# schematic.net
KiCad netlist of a schematic drawn in EAGLE
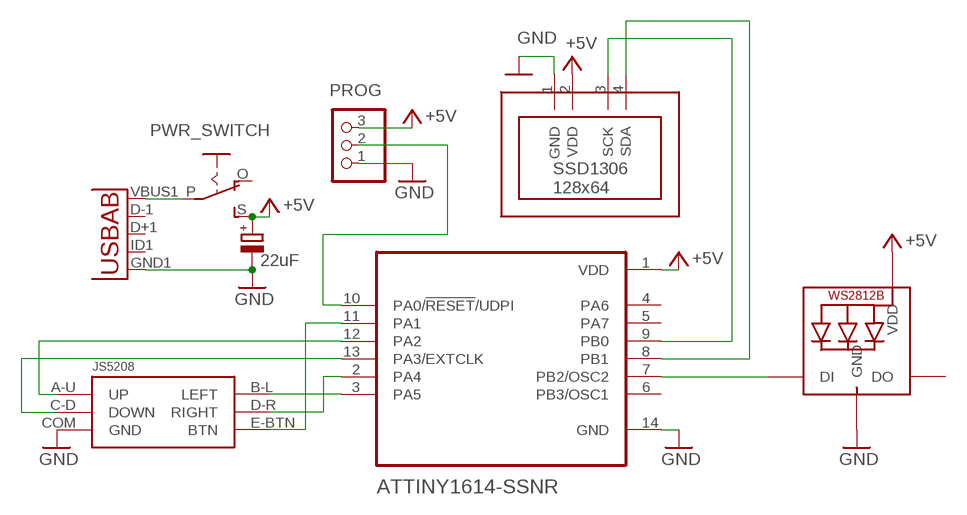
[diagram p0: schematic, sheet 1]

(export (version "E")
  (design (tool "Eeschema 10.0.6"))
  (components
    (comp (ref "C2")
      (value "22uF")
      (footprint "eagle-import:E2-4")
      (libsource (lib "eagle-import") (part "CPOL-EUE2-4"))
    )
    (comp (ref "LED1")
      (value "WS2812B5050")
      (footprint "eagle-import:WS2812B")
      (libsource (lib "eagle-import") (part "WS2812B5050"))
    )
    (comp (ref "PROG")
      (value "PINHD-1X3")
      (footprint "eagle-import:1X03")
      (libsource (lib "eagle-import") (part "PINHD-1X3"))
    )
    (comp (ref "PWR_SWITCH")
      (value "EG1218S")
      (footprint "eagle-import:EG1218")
      (fields (field (name "MF") "E-Switch") (field (name "MP") "EG1218"))
      (libsource (lib "eagle-import") (part "EG1218S"))
    )
    (comp (ref "U$1")
      (value "JS5208")
      (footprint "eagle-import:JS5208_PKG")
      (fields (field (name "MF") "E-Switch"))
      (libsource (lib "eagle-import") (part "JS5208"))
    )
    (comp (ref "U$2")
      (value "SSD1306_128X64_OLEDPINHEAD")
      (footprint "eagle-import:1X04-CLEANBIG")
      (libsource (lib "eagle-import") (part "SSD1306_128X64_OLEDPINHEAD"))
    )
    (comp (ref "U1")
      (value "ATTINY1614-SSNR")
      (footprint "eagle-import:SOIC127P600X175-14N")
      (fields (field (name "MF") "Microchip"))
      (libsource (lib "eagle-import") (part "ATTINY1614-SSNR"))
    )
    (comp (ref "U2")
      (value "USB-THROUGH")
      (footprint "eagle-import:USB-MICRO-THROUGH")
      (libsource (lib "eagle-import") (part "USB-THROUGH"))
    )
  )
  (nets
    (net (code "1") (name "+5V") (class "Default")
      (node (ref "C2") (pin "+") (pinfunction "+_+") (pintype "passive"))
      (node (ref "LED1") (pin "1-VDD") (pinfunction "VDD_1-VDD") (pintype "power_in"))
      (node (ref "PROG") (pin "3") (pinfunction "3_3") (pintype "passive"))
      (node (ref "PWR_SWITCH") (pin "S") (pinfunction "S_S") (pintype "passive"))
      (node (ref "U$2") (pin "2") (pinfunction "VDD_2") (pintype "bidirectional"))
      (node (ref "U1") (pin "1") (pinfunction "VDD_1") (pintype "power_in"))
    )
    (net (code "2") (name "GND") (class "Default")
      (node (ref "C2") (pin "-") (pinfunction "-_-") (pintype "passive"))
      (node (ref "LED1") (pin "3-GND") (pinfunction "GND_3-GND") (pintype "power_in"))
      (node (ref "PROG") (pin "1") (pinfunction "1_1") (pintype "passive"))
      (node (ref "U$1") (pin "COM") (pinfunction "GND_COM") (pintype "bidirectional"))
      (node (ref "U$2") (pin "1") (pinfunction "GND_1") (pintype "bidirectional"))
      (node (ref "U1") (pin "14") (pinfunction "GND_14") (pintype "power_in"))
      (node (ref "U2") (pin "GND1") (pinfunction "GND_GND1") (pintype "bidirectional"))
    )
    (net (code "3") (name "Net-(LED1-DI)") (class "Default")
      (node (ref "LED1") (pin "4-DIN") (pinfunction "DI_4-DIN") (pintype "input"))
      (node (ref "U1") (pin "7") (pinfunction "PB2/OSC2_7") (pintype "bidirectional"))
    )
    (net (code "4") (name "Net-(U$1-BTN)") (class "Default")
      (node (ref "U$1") (pin "E-BTN") (pinfunction "BTN_E-BTN") (pintype "bidirectional"))
      (node (ref "U1") (pin "11") (pinfunction "PA1_11") (pintype "bidirectional"))
    )
    (net (code "5") (name "Net-(U$1-DOWN)") (class "Default")
      (node (ref "U$1") (pin "C-D") (pinfunction "DOWN_C-D") (pintype "bidirectional"))
      (node (ref "U1") (pin "13") (pinfunction "PA3/EXTCLK_13") (pintype "bidirectional"))
    )
    (net (code "6") (name "Net-(U$1-LEFT)") (class "Default")
      (node (ref "U$1") (pin "B-L") (pinfunction "LEFT_B-L") (pintype "bidirectional"))
      (node (ref "U1") (pin "3") (pinfunction "PA5_3") (pintype "bidirectional"))
    )
    (net (code "7") (name "Net-(U$1-RIGHT)") (class "Default")
      (node (ref "U$1") (pin "D-R") (pinfunction "RIGHT_D-R") (pintype "bidirectional"))
      (node (ref "U1") (pin "2") (pinfunction "PA4_2") (pintype "bidirectional"))
    )
    (net (code "8") (name "Net-(U$1-UP)") (class "Default")
      (node (ref "U$1") (pin "A-U") (pinfunction "UP_A-U") (pintype "bidirectional"))
      (node (ref "U1") (pin "12") (pinfunction "PA2_12") (pintype "bidirectional"))
    )
    (net (code "9") (name "Net-(U$2-SCK)") (class "Default")
      (node (ref "U$2") (pin "3") (pinfunction "SCK_3") (pintype "bidirectional"))
      (node (ref "U1") (pin "9") (pinfunction "PB0_9") (pintype "bidirectional"))
    )
    (net (code "10") (name "Net-(U$2-SDA)") (class "Default")
      (node (ref "U$2") (pin "4") (pinfunction "SDA_4") (pintype "bidirectional"))
      (node (ref "U1") (pin "8") (pinfunction "PB1_8") (pintype "bidirectional"))
    )
    (net (code "11") (name "Net-(U1-PA0{slash}~{RESET}{slash}UDPI)") (class "Default")
      (node (ref "PROG") (pin "2") (pinfunction "2_2") (pintype "passive"))
      (node (ref "U1") (pin "10") (pinfunction "PA0/~{RESET}/UDPI_10") (pintype "bidirectional"))
    )
    (net (code "12") (name "Net-(U2-VBUS)") (class "Default")
      (node (ref "PWR_SWITCH") (pin "P") (pinfunction "P_P") (pintype "passive"))
      (node (ref "U2") (pin "VBUS1") (pinfunction "VBUS_VBUS1") (pintype "bidirectional"))
    )
    (net (code "13") (name "unconnected-(LED1-DO-Pad2-DOUT)") (class "Default")
      (node (ref "LED1") (pin "2-DOUT") (pinfunction "DO_2-DOUT") (pintype "output"))
    )
    (net (code "14") (name "unconnected-(PWR_SWITCH-PadO)") (class "Default")
      (node (ref "PWR_SWITCH") (pin "O") (pinfunction "O_O") (pintype "passive"))
    )
    (net (code "15") (name "unconnected-(U1-PA6-Pad4)") (class "Default")
      (node (ref "U1") (pin "4") (pinfunction "PA6_4") (pintype "bidirectional"))
    )
    (net (code "16") (name "unconnected-(U1-PA7-Pad5)") (class "Default")
      (node (ref "U1") (pin "5") (pinfunction "PA7_5") (pintype "bidirectional"))
    )
    (net (code "17") (name "unconnected-(U1-PB3{slash}OSC1-Pad6)") (class "Default")
      (node (ref "U1") (pin "6") (pinfunction "PB3/OSC1_6") (pintype "bidirectional"))
    )
    (net (code "18") (name "unconnected-(U2-D+-PadD+1)") (class "Default")
      (node (ref "U2") (pin "D+1") (pinfunction "D+_D+1") (pintype "bidirectional"))
    )
    (net (code "19") (name "unconnected-(U2-D--PadD-1)") (class "Default")
      (node (ref "U2") (pin "D-1") (pinfunction "D-_D-1") (pintype "bidirectional"))
    )
    (net (code "20") (name "unconnected-(U2-USBID-PadID1)") (class "Default")
      (node (ref "U2") (pin "ID1") (pinfunction "USBID_ID1") (pintype "bidirectional"))
    )
  )
)
